# Sheet1.net
KiCad netlist of a schematic drawn in Altium Designer
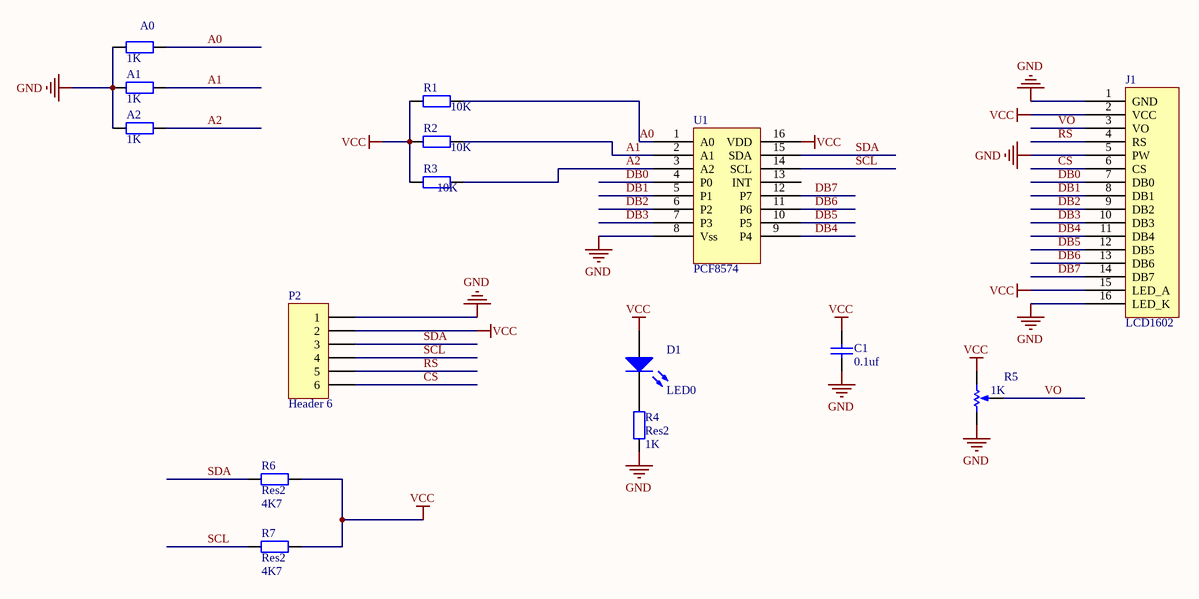
[diagram p0: Sheet1.SchDoc]

(export (version "E")
  (design (tool "Eeschema 10.0.6"))
  (components
    (comp (ref "A0")
      (value "1K")
      (footprint "C0805")
      (description "Resistor")
      (fields (field (name "Comment") "Res2") (field (name "PUBLISHER") "Altium Limited"))
      (libsource (lib "Miscellaneous Devices") (part "Res2"))
    )
    (comp (ref "A1")
      (value "1K")
      (footprint "C0805")
      (description "Resistor")
      (fields (field (name "Comment") "Res2") (field (name "PUBLISHER") "Altium Limited"))
      (libsource (lib "Miscellaneous Devices") (part "Res2"))
    )
    (comp (ref "A2")
      (value "1K")
      (footprint "C0805")
      (description "Resistor")
      (fields (field (name "Comment") "Res2") (field (name "PUBLISHER") "Altium Limited"))
      (libsource (lib "Miscellaneous Devices") (part "Res2"))
    )
    (comp (ref "C1")
      (value "0.1uf")
      (footprint "C0805")
      (description "Capacitor (Semiconductor SIM Model)")
      (fields (field (name "Comment") "Cap Semi") (field (name "PUBLISHER") "Altium Limited"))
      (libsource (lib "Miscellaneous Devices") (part "Cap Semi"))
    )
    (comp (ref "D1")
      (value "LED0")
      (footprint "CAPR5-4X5")
      (description "Typical INFRARED GaAs LED")
      (fields (field (name "PUBLISHER") "Altium Limited"))
      (libsource (lib "Miscellaneous Devices") (part "LED0"))
    )
    (comp (ref "J1") (value "LCD1602") (footprint "HDR1X16") (libsource (lib "Schlib1") (part "Component_2")))
    (comp (ref "P2")
      (value "Header 6")
      (footprint "HDR1X6")
      (description "Header, 6-Pin")
      (fields (field (name "PUBLISHER") "Altium Limited"))
      (libsource (lib "Miscellaneous Connectors") (part "Header 6"))
    )
    (comp (ref "R1")
      (value "10K")
      (footprint "C0805")
      (description "Resistor")
      (fields (field (name "Comment") "Res2") (field (name "PUBLISHER") "Altium Limited"))
      (libsource (lib "Miscellaneous Devices") (part "Res2"))
    )
    (comp (ref "R2")
      (value "10K")
      (footprint "C0805")
      (description "Resistor")
      (fields (field (name "Comment") "Res2") (field (name "PUBLISHER") "Altium Limited"))
      (libsource (lib "Miscellaneous Devices") (part "Res2"))
    )
    (comp (ref "R3")
      (value "10K")
      (footprint "C0805")
      (description "Resistor")
      (fields (field (name "Comment") "Res2") (field (name "PUBLISHER") "Altium Limited"))
      (libsource (lib "Miscellaneous Devices") (part "Res2"))
    )
    (comp (ref "R4")
      (value "Res2")
      (footprint "C0805")
      (description "Resistor")
      (fields (field (name "ALTIUM_VALUE") "1K") (field (name "PUBLISHER") "Altium Limited"))
      (libsource (lib "") (part "Res2_1"))
    )
    (comp (ref "R5")
      (value "1K")
      (footprint "HDR1X3")
      (description "Potentiometer")
      (fields (field (name "Comment") "RPot") (field (name "PUBLISHER") "Altium Limited"))
      (libsource (lib "Miscellaneous Devices") (part "RPot"))
    )
    (comp (ref "R6")
      (value "Res2")
      (footprint "C0805")
      (description "Resistor")
      (fields (field (name "ALTIUM_VALUE") "4K7") (field (name "PUBLISHER") "Altium Limited"))
      (libsource (lib "Miscellaneous Devices") (part "Res2"))
    )
    (comp (ref "R7")
      (value "Res2")
      (footprint "C0805")
      (description "Resistor")
      (fields (field (name "ALTIUM_VALUE") "4K7") (field (name "PUBLISHER") "Altium Limited"))
      (libsource (lib "Miscellaneous Devices") (part "Res2"))
    )
    (comp (ref "U1") (value "PCF8574") (footprint "PCF8574") (libsource (lib "Schlib1") (part "Component_1")))
  )
  (nets
    (net (code "1") (name "/A0") (class "Default")
      (node (ref "A0") (pin "2") (pinfunction "2_2") (pintype "passive"))
      (node (ref "R1") (pin "2") (pinfunction "2_2") (pintype "passive"))
      (node (ref "U1") (pin "1") (pinfunction "A0_1") (pintype "passive"))
    )
    (net (code "2") (name "/A1") (class "Default")
      (node (ref "A1") (pin "2") (pinfunction "2_2") (pintype "passive"))
      (node (ref "R2") (pin "2") (pinfunction "2_2") (pintype "passive"))
      (node (ref "U1") (pin "2") (pinfunction "A1_2") (pintype "passive"))
    )
    (net (code "3") (name "/A2") (class "Default")
      (node (ref "A2") (pin "2") (pinfunction "2_2") (pintype "passive"))
      (node (ref "R3") (pin "2") (pinfunction "2_2") (pintype "passive"))
      (node (ref "U1") (pin "3") (pinfunction "A2_3") (pintype "passive"))
    )
    (net (code "4") (name "/CS") (class "Default")
      (node (ref "J1") (pin "6") (pinfunction "CS_6") (pintype "passive"))
      (node (ref "P2") (pin "6") (pinfunction "6_6") (pintype "passive"))
    )
    (net (code "5") (name "/DB0") (class "Default")
      (node (ref "J1") (pin "7") (pinfunction "DB0_7") (pintype "passive"))
      (node (ref "U1") (pin "4") (pinfunction "P0_4") (pintype "passive"))
    )
    (net (code "6") (name "/DB1") (class "Default")
      (node (ref "J1") (pin "8") (pinfunction "DB1_8") (pintype "passive"))
      (node (ref "U1") (pin "5") (pinfunction "P1_5") (pintype "passive"))
    )
    (net (code "7") (name "/DB2") (class "Default")
      (node (ref "J1") (pin "9") (pinfunction "DB2_9") (pintype "passive"))
      (node (ref "U1") (pin "6") (pinfunction "P2_6") (pintype "passive"))
    )
    (net (code "8") (name "/DB3") (class "Default")
      (node (ref "J1") (pin "10") (pinfunction "DB3_10") (pintype "passive"))
      (node (ref "U1") (pin "7") (pinfunction "P3_7") (pintype "passive"))
    )
    (net (code "9") (name "/DB4") (class "Default")
      (node (ref "J1") (pin "11") (pinfunction "DB4_11") (pintype "passive"))
      (node (ref "U1") (pin "9") (pinfunction "P4_9") (pintype "passive"))
    )
    (net (code "10") (name "/DB5") (class "Default")
      (node (ref "J1") (pin "12") (pinfunction "DB5_12") (pintype "passive"))
      (node (ref "U1") (pin "10") (pinfunction "P5_10") (pintype "passive"))
    )
    (net (code "11") (name "/DB6") (class "Default")
      (node (ref "J1") (pin "13") (pinfunction "DB6_13") (pintype "passive"))
      (node (ref "U1") (pin "11") (pinfunction "P6_11") (pintype "passive"))
    )
    (net (code "12") (name "/DB7") (class "Default")
      (node (ref "J1") (pin "14") (pinfunction "DB7_14") (pintype "passive"))
      (node (ref "U1") (pin "12") (pinfunction "P7_12") (pintype "passive"))
    )
    (net (code "13") (name "/RS") (class "Default")
      (node (ref "J1") (pin "4") (pinfunction "RS_4") (pintype "passive"))
      (node (ref "P2") (pin "5") (pinfunction "5_5") (pintype "passive"))
    )
    (net (code "14") (name "/SCL") (class "Default")
      (node (ref "P2") (pin "4") (pinfunction "4_4") (pintype "passive"))
      (node (ref "R7") (pin "1") (pinfunction "1_1") (pintype "passive"))
      (node (ref "U1") (pin "14") (pinfunction "SCL_14") (pintype "passive"))
    )
    (net (code "15") (name "/SDA") (class "Default")
      (node (ref "P2") (pin "3") (pinfunction "3_3") (pintype "passive"))
      (node (ref "R6") (pin "1") (pinfunction "1_1") (pintype "passive"))
      (node (ref "U1") (pin "15") (pinfunction "SDA_15") (pintype "passive"))
    )
    (net (code "16") (name "/VO") (class "Default")
      (node (ref "J1") (pin "3") (pinfunction "VO_3") (pintype "passive"))
      (node (ref "R5") (pin "3") (pinfunction "TAP_3") (pintype "passive"))
    )
    (net (code "17") (name "GND") (class "Default")
      (node (ref "A0") (pin "1") (pinfunction "1_1") (pintype "passive"))
      (node (ref "A1") (pin "1") (pinfunction "1_1") (pintype "passive"))
      (node (ref "A2") (pin "1") (pinfunction "1_1") (pintype "passive"))
      (node (ref "C1") (pin "1") (pinfunction "1_1") (pintype "passive"))
      (node (ref "J1") (pin "1") (pinfunction "GND_1") (pintype "passive"))
      (node (ref "J1") (pin "16") (pinfunction "LED_K_16") (pintype "passive"))
      (node (ref "J1") (pin "5") (pinfunction "PW_5") (pintype "passive"))
      (node (ref "P2") (pin "1") (pinfunction "1_1") (pintype "passive"))
      (node (ref "R4") (pin "1") (pinfunction "1_1") (pintype "passive"))
      (node (ref "R5") (pin "1") (pinfunction "TOP_1") (pintype "passive"))
      (node (ref "U1") (pin "8") (pinfunction "Vss_8") (pintype "passive"))
    )
    (net (code "18") (name "Net-(D1-K)") (class "Default")
      (node (ref "D1") (pin "2") (pinfunction "K_2") (pintype "passive"))
      (node (ref "R4") (pin "2") (pinfunction "2_2") (pintype "passive"))
    )
    (net (code "19") (name "VCC") (class "Default")
      (node (ref "C1") (pin "2") (pinfunction "2_2") (pintype "passive"))
      (node (ref "D1") (pin "1") (pinfunction "A_1") (pintype "passive"))
      (node (ref "J1") (pin "15") (pinfunction "LED_A_15") (pintype "passive"))
      (node (ref "J1") (pin "2") (pinfunction "VCC_2") (pintype "passive"))
      (node (ref "P2") (pin "2") (pinfunction "2_2") (pintype "passive"))
      (node (ref "R1") (pin "1") (pinfunction "1_1") (pintype "passive"))
      (node (ref "R2") (pin "1") (pinfunction "1_1") (pintype "passive"))
      (node (ref "R3") (pin "1") (pinfunction "1_1") (pintype "passive"))
      (node (ref "R5") (pin "2") (pinfunction "BOT_2") (pintype "passive"))
      (node (ref "R6") (pin "2") (pinfunction "2_2") (pintype "passive"))
      (node (ref "R7") (pin "2") (pinfunction "2_2") (pintype "passive"))
      (node (ref "U1") (pin "16") (pinfunction "VDD_16") (pintype "passive"))
    )
    (net (code "20") (name "unconnected-(U1-INT-Pad13)") (class "Default")
      (node (ref "U1") (pin "13") (pinfunction "INT_13") (pintype "passive"))
    )
  )
)
